# rfamp.net
KiCad netlist of a schematic drawn in EAGLE
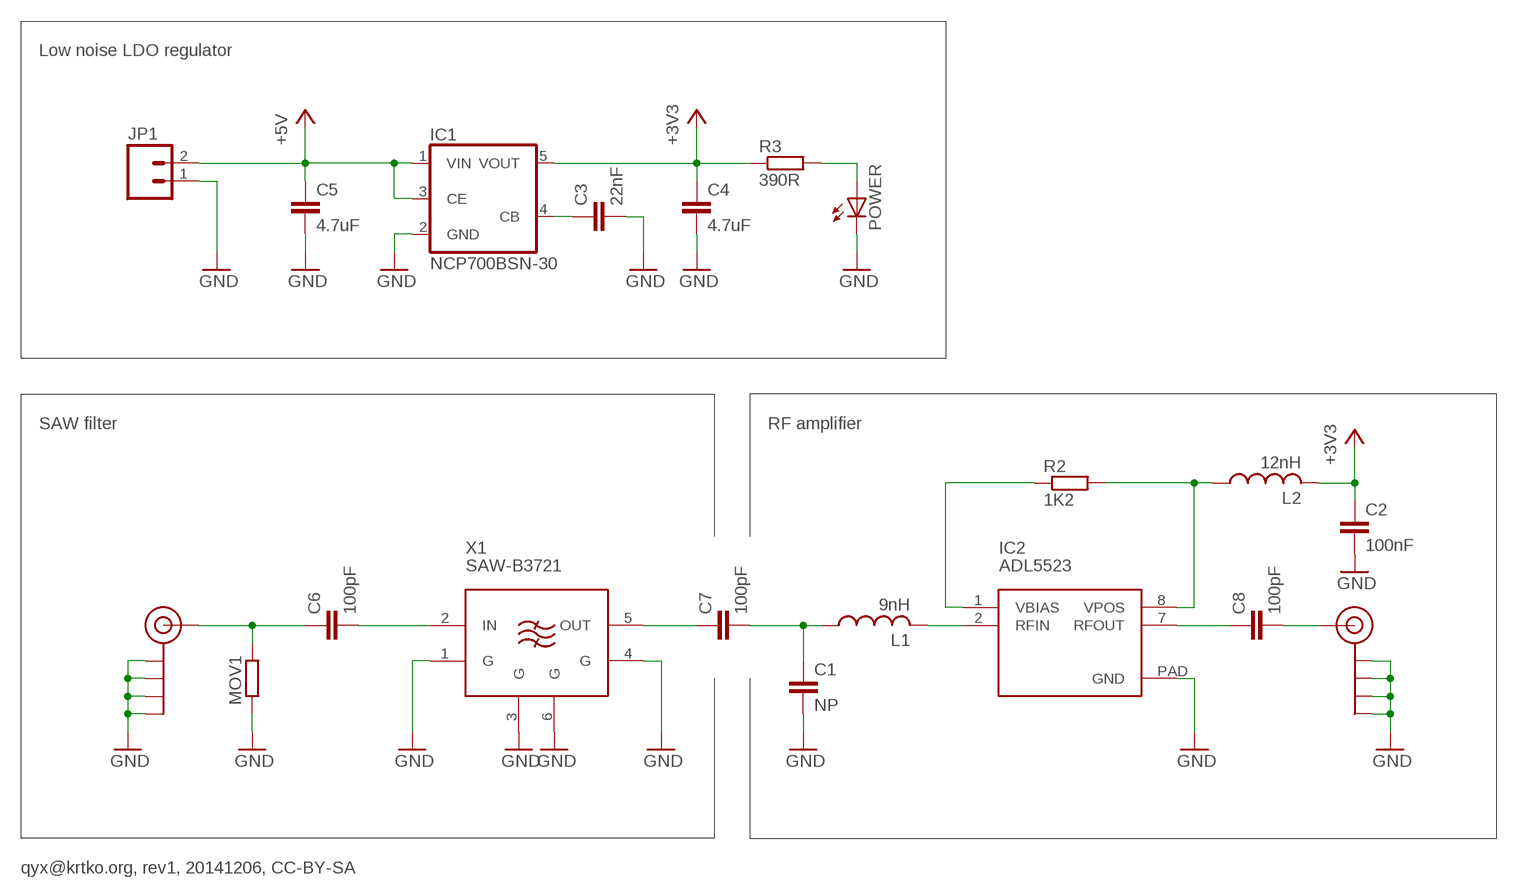
[diagram p0: schematic, sheet 1]

(export (version "E")
  (design (tool "Eeschema 10.0.6"))
  (components
    (comp (ref "C1")
      (value "NP")
      (footprint "eagle-import:C0603")
      (libsource (lib "eagle-import") (part "C-EUC0603"))
    )
    (comp (ref "C2")
      (value "100nF")
      (footprint "eagle-import:C0603")
      (libsource (lib "eagle-import") (part "C-EUC0603"))
    )
    (comp (ref "C3")
      (value "22nF")
      (footprint "eagle-import:C0603")
      (libsource (lib "eagle-import") (part "C-EUC0603"))
    )
    (comp (ref "C4")
      (value "4.7uF")
      (footprint "eagle-import:C0805")
      (libsource (lib "eagle-import") (part "C-EUC0805"))
    )
    (comp (ref "C5")
      (value "4.7uF")
      (footprint "eagle-import:C0805")
      (libsource (lib "eagle-import") (part "C-EUC0805"))
    )
    (comp (ref "C6")
      (value "100pF")
      (footprint "eagle-import:C0603")
      (libsource (lib "eagle-import") (part "C-EUC0603"))
    )
    (comp (ref "C7")
      (value "100pF")
      (footprint "eagle-import:C0603")
      (libsource (lib "eagle-import") (part "C-EUC0603"))
    )
    (comp (ref "C8")
      (value "100pF")
      (footprint "eagle-import:C0603")
      (libsource (lib "eagle-import") (part "C-EUC0603"))
    )
    (comp (ref "IC1")
      (value "NCP700BSN-30")
      (footprint "eagle-import:SOT25")
      (libsource (lib "eagle-import") (part "TS520530"))
    )
    (comp (ref "IC2")
      (value "ADL5523")
      (footprint "eagle-import:LFCSP_VD_8")
      (libsource (lib "eagle-import") (part "ADL5523"))
    )
    (comp (ref "J$1")
      (value "SMA_EDGE")
      (footprint "eagle-import:SMA-EDGE")
      (libsource (lib "eagle-import") (part "SMA_EDGE"))
    )
    (comp (ref "J$2")
      (value "SMA_EDGE")
      (footprint "eagle-import:SMA-EDGE")
      (libsource (lib "eagle-import") (part "SMA_EDGE"))
    )
    (comp (ref "JP1")
      (value "M02JST-PTH-2")
      (footprint "eagle-import:JST-2-PTH")
      (libsource (lib "eagle-import") (part "M02JST-PTH-2"))
    )
    (comp (ref "L1")
      (value "9nH")
      (footprint "eagle-import:L2012C")
      (libsource (lib "eagle-import") (part "L-USL2012C"))
    )
    (comp (ref "L2")
      (value "12nH")
      (footprint "eagle-import:L2012C")
      (libsource (lib "eagle-import") (part "L-USL2012C"))
    )
    (comp (ref "MOV1")
      (value "R-EU_R0603")
      (footprint "eagle-import:R0603")
      (libsource (lib "eagle-import") (part "R-EU_R0603"))
    )
    (comp (ref "POWER")
      (value "LEDCHIPLED_0603")
      (footprint "eagle-import:CHIPLED_0603")
      (libsource (lib "eagle-import") (part "LEDCHIPLED_0603"))
    )
    (comp (ref "R2")
      (value "1K2")
      (footprint "eagle-import:R0603")
      (libsource (lib "eagle-import") (part "R-EU_R0603"))
    )
    (comp (ref "R3")
      (value "390R")
      (footprint "eagle-import:R0603")
      (libsource (lib "eagle-import") (part "R-EU_R0603"))
    )
    (comp (ref "X1")
      (value "SAW-B3721")
      (footprint "eagle-import:B3721")
      (libsource (lib "eagle-import") (part "SAW-B3721"))
    )
  )
  (nets
    (net (code "1") (name "+3V3") (class "Default")
      (node (ref "C2") (pin "1") (pinfunction "1_1") (pintype "passive"))
      (node (ref "C4") (pin "1") (pinfunction "1_1") (pintype "passive"))
      (node (ref "IC1") (pin "5") (pinfunction "VOUT_5") (pintype "passive"))
      (node (ref "L2") (pin "2") (pinfunction "2_2") (pintype "passive"))
      (node (ref "R3") (pin "1") (pinfunction "1_1") (pintype "passive"))
    )
    (net (code "2") (name "+5V") (class "Default")
      (node (ref "C5") (pin "1") (pinfunction "1_1") (pintype "passive"))
      (node (ref "IC1") (pin "1") (pinfunction "VIN_1") (pintype "input"))
      (node (ref "IC1") (pin "3") (pinfunction "CE_3") (pintype "input"))
      (node (ref "JP1") (pin "2") (pinfunction "2_2") (pintype "passive"))
    )
    (net (code "3") (name "GND") (class "Default")
      (node (ref "C1") (pin "2") (pinfunction "2_2") (pintype "passive"))
      (node (ref "C2") (pin "2") (pinfunction "2_2") (pintype "passive"))
      (node (ref "C3") (pin "2") (pinfunction "2_2") (pintype "passive"))
      (node (ref "C4") (pin "2") (pinfunction "2_2") (pintype "passive"))
      (node (ref "C5") (pin "2") (pinfunction "2_2") (pintype "passive"))
      (node (ref "IC1") (pin "2") (pinfunction "GND_2") (pintype "passive"))
      (node (ref "IC2") (pin "PAD") (pinfunction "GND_PAD") (pintype "bidirectional"))
      (node (ref "J$1") (pin "GND@0") (pinfunction "GND_GND@0") (pintype "bidirectional"))
      (node (ref "J$1") (pin "GND@1") (pinfunction "GND_GND@1") (pintype "bidirectional"))
      (node (ref "J$1") (pin "GND@2") (pinfunction "GND_GND@2") (pintype "bidirectional"))
      (node (ref "J$1") (pin "GND@3") (pinfunction "GND_GND@3") (pintype "bidirectional"))
      (node (ref "J$2") (pin "GND@0") (pinfunction "GND_GND@0") (pintype "bidirectional"))
      (node (ref "J$2") (pin "GND@1") (pinfunction "GND_GND@1") (pintype "bidirectional"))
      (node (ref "J$2") (pin "GND@2") (pinfunction "GND_GND@2") (pintype "bidirectional"))
      (node (ref "J$2") (pin "GND@3") (pinfunction "GND_GND@3") (pintype "bidirectional"))
      (node (ref "JP1") (pin "1") (pinfunction "1_1") (pintype "passive"))
      (node (ref "MOV1") (pin "1") (pinfunction "1_1") (pintype "passive"))
      (node (ref "POWER") (pin "C") (pinfunction "C_C") (pintype "passive"))
      (node (ref "X1") (pin "1") (pinfunction "G_1") (pintype "bidirectional"))
      (node (ref "X1") (pin "3") (pinfunction "G_3") (pintype "bidirectional"))
      (node (ref "X1") (pin "4") (pinfunction "G_4") (pintype "bidirectional"))
      (node (ref "X1") (pin "6") (pinfunction "G_6") (pintype "bidirectional"))
    )
    (net (code "4") (name "Net-(C1-Pad1)") (class "Default")
      (node (ref "C1") (pin "1") (pinfunction "1_1") (pintype "passive"))
      (node (ref "C7") (pin "2") (pinfunction "2_2") (pintype "passive"))
      (node (ref "L1") (pin "1") (pinfunction "1_1") (pintype "passive"))
    )
    (net (code "5") (name "Net-(IC1-CB)") (class "Default")
      (node (ref "C3") (pin "1") (pinfunction "1_1") (pintype "passive"))
      (node (ref "IC1") (pin "4") (pinfunction "CB_4") (pintype "input"))
    )
    (net (code "6") (name "Net-(IC2-RFIN)") (class "Default")
      (node (ref "IC2") (pin "2") (pinfunction "RFIN_2") (pintype "bidirectional"))
      (node (ref "L1") (pin "2") (pinfunction "2_2") (pintype "passive"))
    )
    (net (code "7") (name "Net-(IC2-RFOUT)") (class "Default")
      (node (ref "C8") (pin "1") (pinfunction "1_1") (pintype "passive"))
      (node (ref "IC2") (pin "7") (pinfunction "RFOUT_7") (pintype "bidirectional"))
    )
    (net (code "8") (name "Net-(IC2-VBIAS)") (class "Default")
      (node (ref "IC2") (pin "1") (pinfunction "VBIAS_1") (pintype "bidirectional"))
      (node (ref "R2") (pin "1") (pinfunction "1_1") (pintype "passive"))
    )
    (net (code "9") (name "Net-(IC2-VPOS)") (class "Default")
      (node (ref "IC2") (pin "8") (pinfunction "VPOS_8") (pintype "bidirectional"))
      (node (ref "L2") (pin "1") (pinfunction "1_1") (pintype "passive"))
      (node (ref "R2") (pin "2") (pinfunction "2_2") (pintype "passive"))
    )
    (net (code "10") (name "Net-(J$1-SIGNAL)") (class "Default")
      (node (ref "C6") (pin "1") (pinfunction "1_1") (pintype "passive"))
      (node (ref "J$1") (pin "SIG") (pinfunction "SIGNAL_SIG") (pintype "bidirectional"))
      (node (ref "MOV1") (pin "2") (pinfunction "2_2") (pintype "passive"))
    )
    (net (code "11") (name "Net-(J$2-SIGNAL)") (class "Default")
      (node (ref "C8") (pin "2") (pinfunction "2_2") (pintype "passive"))
      (node (ref "J$2") (pin "SIG") (pinfunction "SIGNAL_SIG") (pintype "bidirectional"))
    )
    (net (code "12") (name "Net-(POWER-PadA)") (class "Default")
      (node (ref "POWER") (pin "A") (pinfunction "A_A") (pintype "passive"))
      (node (ref "R3") (pin "2") (pinfunction "2_2") (pintype "passive"))
    )
    (net (code "13") (name "Net-(X1-IN)") (class "Default")
      (node (ref "C6") (pin "2") (pinfunction "2_2") (pintype "passive"))
      (node (ref "X1") (pin "2") (pinfunction "IN_2") (pintype "bidirectional"))
    )
    (net (code "14") (name "Net-(X1-OUT)") (class "Default")
      (node (ref "C7") (pin "1") (pinfunction "1_1") (pintype "passive"))
      (node (ref "X1") (pin "5") (pinfunction "OUT_5") (pintype "bidirectional"))
    )
  )
)
